# MainSheet.net
KiCad netlist of a schematic drawn in Altium Designer
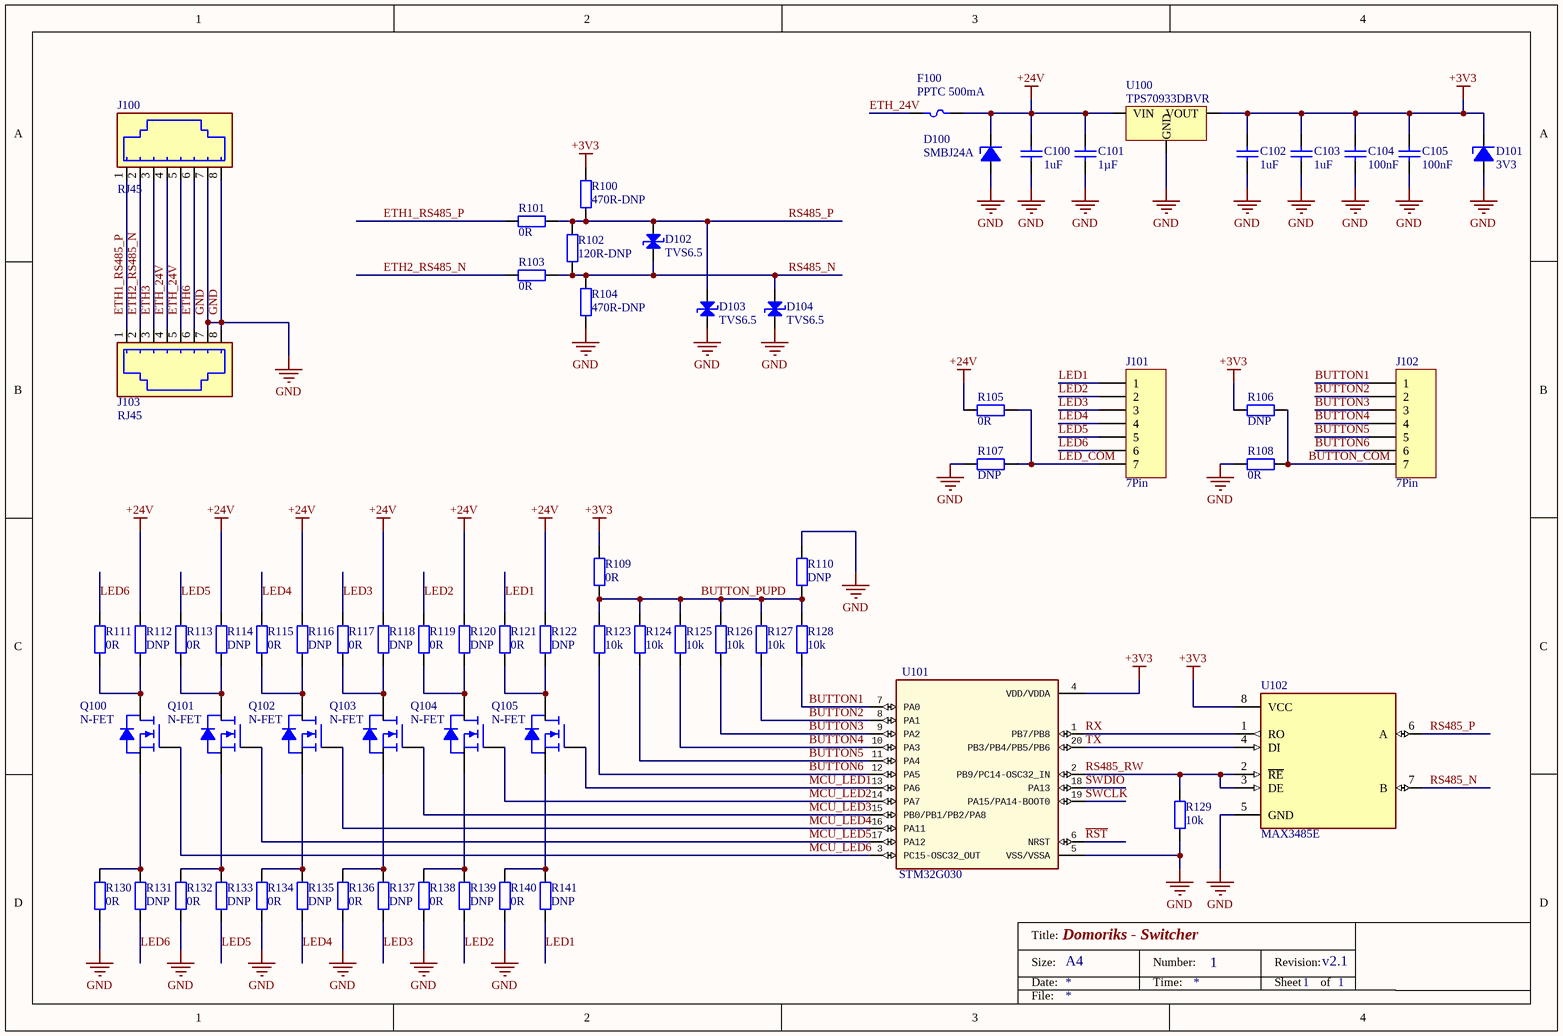
[diagram p0: MainSheet.SchDoc]

(export (version "E")
  (design (tool "Eeschema 10.0.6"))
  (components
    (comp (ref "C100") (value "1uF") (footprint "C0603") (libsource (lib "Library") (part "Capacitor")))
    (comp (ref "C101") (value "1µF") (footprint "C0603") (libsource (lib "Library") (part "Capacitor")))
    (comp (ref "C102") (value "1uF") (footprint "C0603") (libsource (lib "Library") (part "Capacitor")))
    (comp (ref "C103") (value "1uF") (footprint "C0603") (libsource (lib "Library") (part "Capacitor")))
    (comp (ref "C104") (value "100nF") (footprint "C0603") (libsource (lib "Library") (part "Capacitor")))
    (comp (ref "C105") (value "100nF") (footprint "C0603") (libsource (lib "Library") (part "Capacitor")))
    (comp (ref "D100") (value "SMBJ24A") (footprint "SMB") (libsource (lib "Library") (part "TVS Uni")))
    (comp (ref "D101") (value "3V3") (footprint "SOD323") (libsource (lib "MyLib") (part "TVS Uni")))
    (comp (ref "D102") (value "TVS6.5") (footprint "SOD323") (libsource (lib "Library") (part "TVS Bi")))
    (comp (ref "D103") (value "TVS6.5") (footprint "SOD323") (libsource (lib "Library") (part "TVS Bi")))
    (comp (ref "D104") (value "TVS6.5") (footprint "SOD323") (libsource (lib "Library") (part "TVS Bi")))
    (comp (ref "F100") (value "PPTC 500mA") (footprint "PPTC1812") (libsource (lib "Library") (part "Fuse")))
    (comp (ref "J100")
      (value "RJ45")
      (footprint "RJ45_RA")
      (description "Jack Modular Connector 8p8c (RJ45, Ethernet) Vertical Unshielded Cat5")
      (fields (field (name "MF") "Wurth Elektronik") (field (name "MP") "615008144221"))
      (libsource (lib "Library") (part "RJ45"))
    )
    (comp (ref "J101") (value "7Pin") (footprint "7Pin") (libsource (lib "Library") (part "7Pin")))
    (comp (ref "J102") (value "7Pin") (footprint "7Pin") (libsource (lib "Library") (part "7Pin")))
    (comp (ref "J103")
      (value "RJ45")
      (footprint "RJ45_RA")
      (description "Jack Modular Connector 8p8c (RJ45, Ethernet) Vertical Unshielded Cat5")
      (fields (field (name "MF") "Wurth Elektronik") (field (name "MP") "615008144221"))
      (libsource (lib "") (part "RJ45_1"))
    )
    (comp (ref "Q100") (value "N-FET") (footprint "SOT323") (libsource (lib "Library") (part "N-FET")))
    (comp (ref "Q101") (value "N-FET") (footprint "SOT323") (libsource (lib "Library") (part "N-FET")))
    (comp (ref "Q102") (value "N-FET") (footprint "SOT323") (libsource (lib "Library") (part "N-FET")))
    (comp (ref "Q103") (value "N-FET") (footprint "SOT323") (libsource (lib "Library") (part "N-FET")))
    (comp (ref "Q104") (value "N-FET") (footprint "SOT323") (libsource (lib "Library") (part "N-FET")))
    (comp (ref "Q105") (value "N-FET") (footprint "SOT323") (libsource (lib "Library") (part "N-FET")))
    (comp (ref "R100") (value "470R-DNP") (footprint "R0603") (libsource (lib "") (part "Resistor_2")))
    (comp (ref "R101") (value "0R") (footprint "R0603") (libsource (lib "Library") (part "Resistor")))
    (comp (ref "R102") (value "120R-DNP") (footprint "R0603") (libsource (lib "") (part "Resistor_2")))
    (comp (ref "R103") (value "0R") (footprint "R0603") (libsource (lib "Library") (part "Resistor")))
    (comp (ref "R104") (value "470R-DNP") (footprint "R0603") (libsource (lib "") (part "Resistor_2")))
    (comp (ref "R105") (value "0R") (footprint "R0603") (libsource (lib "") (part "Resistor_1")))
    (comp (ref "R106") (value "DNP") (footprint "R0603") (libsource (lib "") (part "Resistor_1")))
    (comp (ref "R107") (value "DNP") (footprint "R0603") (libsource (lib "") (part "Resistor_1")))
    (comp (ref "R108") (value "0R") (footprint "R0603") (libsource (lib "") (part "Resistor_1")))
    (comp (ref "R109") (value "0R") (footprint "R0603") (libsource (lib "Library") (part "Resistor")))
    (comp (ref "R110") (value "DNP") (footprint "R0603") (libsource (lib "Library") (part "Resistor")))
    (comp (ref "R111") (value "0R") (footprint "R0603") (libsource (lib "Library") (part "Resistor")))
    (comp (ref "R112") (value "DNP") (footprint "R0603") (libsource (lib "Library") (part "Resistor")))
    (comp (ref "R113") (value "0R") (footprint "R0603") (libsource (lib "Library") (part "Resistor")))
    (comp (ref "R114") (value "DNP") (footprint "R0603") (libsource (lib "Library") (part "Resistor")))
    (comp (ref "R115") (value "0R") (footprint "R0603") (libsource (lib "Library") (part "Resistor")))
    (comp (ref "R116") (value "DNP") (footprint "R0603") (libsource (lib "Library") (part "Resistor")))
    (comp (ref "R117") (value "0R") (footprint "R0603") (libsource (lib "Library") (part "Resistor")))
    (comp (ref "R118") (value "DNP") (footprint "R0603") (libsource (lib "Library") (part "Resistor")))
    (comp (ref "R119") (value "0R") (footprint "R0603") (libsource (lib "Library") (part "Resistor")))
    (comp (ref "R120") (value "DNP") (footprint "R0603") (libsource (lib "Library") (part "Resistor")))
    (comp (ref "R121") (value "0R") (footprint "R0603") (libsource (lib "Library") (part "Resistor")))
    (comp (ref "R122") (value "DNP") (footprint "R0603") (libsource (lib "Library") (part "Resistor")))
    (comp (ref "R123") (value "10k") (footprint "R0603") (libsource (lib "Library") (part "Resistor")))
    (comp (ref "R124") (value "10k") (footprint "R0603") (libsource (lib "Library") (part "Resistor")))
    (comp (ref "R125") (value "10k") (footprint "R0603") (libsource (lib "Library") (part "Resistor")))
    (comp (ref "R126") (value "10k") (footprint "R0603") (libsource (lib "Library") (part "Resistor")))
    (comp (ref "R127") (value "10k") (footprint "R0603") (libsource (lib "Library") (part "Resistor")))
    (comp (ref "R128") (value "10k") (footprint "R0603") (libsource (lib "Library") (part "Resistor")))
    (comp (ref "R129") (value "10k") (footprint "R0603") (libsource (lib "Library") (part "Resistor")))
    (comp (ref "R130") (value "0R") (footprint "R0603") (libsource (lib "Library") (part "Resistor")))
    (comp (ref "R131") (value "DNP") (footprint "R0603") (libsource (lib "Library") (part "Resistor")))
    (comp (ref "R132") (value "0R") (footprint "R0603") (libsource (lib "Library") (part "Resistor")))
    (comp (ref "R133") (value "DNP") (footprint "R0603") (libsource (lib "Library") (part "Resistor")))
    (comp (ref "R134") (value "0R") (footprint "R0603") (libsource (lib "Library") (part "Resistor")))
    (comp (ref "R135") (value "DNP") (footprint "R0603") (libsource (lib "Library") (part "Resistor")))
    (comp (ref "R136") (value "0R") (footprint "R0603") (libsource (lib "Library") (part "Resistor")))
    (comp (ref "R137") (value "DNP") (footprint "R0603") (libsource (lib "Library") (part "Resistor")))
    (comp (ref "R138") (value "0R") (footprint "R0603") (libsource (lib "Library") (part "Resistor")))
    (comp (ref "R139") (value "DNP") (footprint "R0603") (libsource (lib "Library") (part "Resistor")))
    (comp (ref "R140") (value "0R") (footprint "R0603") (libsource (lib "Library") (part "Resistor")))
    (comp (ref "R141") (value "DNP") (footprint "R0603") (libsource (lib "Library") (part "Resistor")))
    (comp (ref "U100")
      (value "TPS70933DBVR")
      (footprint "SOT-23-5")
      (fields (field (name "MP") "LP38690DT-5.0/NOPB") (field (name "MF") "Texas Instruments"))
      (libsource (lib "Schlib1") (part "LDO"))
    )
    (comp (ref "U101")
      (value "STM32G030")
      (footprint "TSSOP20")
      (fields
        (field (name "MANUFACTURER_PART_NUMBER") "STM32G030F6P6TR")
        (field (name "COPYRIGHT") "Copyright (C) 2022 Ultra Librarian. All rights reserved.")
      )
      (libsource (lib "Schlib1") (part "STM32G030"))
    )
    (comp (ref "U102")
      (value "MAX3485E")
      (footprint "SOIC-08")
      (description "1/1 Transceiver Half RS422, RS485 8-SOIC")
      (fields (field (name "MF") "Maxim Integrated") (field (name "MP") "MAX3485EESA+T"))
      (libsource (lib "Library") (part "MAX3485E"))
    )
  )
  (nets
    (net (code "1") (name "+3V3") (class "Default")
      (node (ref "C102") (pin "2") (pinfunction "2_2") (pintype "passive"))
      (node (ref "C103") (pin "2") (pinfunction "2_2") (pintype "passive"))
      (node (ref "C104") (pin "2") (pinfunction "2_2") (pintype "passive"))
      (node (ref "C105") (pin "2") (pinfunction "2_2") (pintype "passive"))
      (node (ref "D101") (pin "1") (pinfunction "1_1") (pintype "passive"))
      (node (ref "R100") (pin "2") (pinfunction "2_2") (pintype "passive"))
      (node (ref "R106") (pin "2") (pinfunction "2_2") (pintype "passive"))
      (node (ref "R109") (pin "2") (pinfunction "2_2") (pintype "passive"))
      (node (ref "U100") (pin "5") (pinfunction "VOUT_5") (pintype "power_in"))
      (node (ref "U101") (pin "4") (pinfunction "VDD/VDDA_4") (pintype "power_in"))
      (node (ref "U102") (pin "8") (pinfunction "VCC_8") (pintype "power_in"))
    )
    (net (code "2") (name "+24V") (class "Default")
      (node (ref "C100") (pin "2") (pinfunction "2_2") (pintype "passive"))
      (node (ref "C101") (pin "2") (pinfunction "2_2") (pintype "passive"))
      (node (ref "D100") (pin "1") (pinfunction "1_1") (pintype "passive"))
      (node (ref "F100") (pin "2") (pinfunction "2_2") (pintype "passive"))
      (node (ref "R105") (pin "2") (pinfunction "2_2") (pintype "passive"))
      (node (ref "R112") (pin "2") (pinfunction "2_2") (pintype "passive"))
      (node (ref "R114") (pin "2") (pinfunction "2_2") (pintype "passive"))
      (node (ref "R116") (pin "2") (pinfunction "2_2") (pintype "passive"))
      (node (ref "R118") (pin "2") (pinfunction "2_2") (pintype "passive"))
      (node (ref "R120") (pin "2") (pinfunction "2_2") (pintype "passive"))
      (node (ref "R122") (pin "2") (pinfunction "2_2") (pintype "passive"))
      (node (ref "U100") (pin "1") (pinfunction "VIN_1") (pintype "power_in"))
    )
    (net (code "3") (name "/BUTTON1") (class "Default")
      (node (ref "J102") (pin "1") (pinfunction "1_1") (pintype "passive"))
      (node (ref "R128") (pin "1") (pinfunction "1_1") (pintype "passive"))
      (node (ref "U101") (pin "7") (pinfunction "PA0_7") (pintype "bidirectional"))
    )
    (net (code "4") (name "/BUTTON2") (class "Default")
      (node (ref "J102") (pin "2") (pinfunction "2_2") (pintype "passive"))
      (node (ref "R127") (pin "1") (pinfunction "1_1") (pintype "passive"))
      (node (ref "U101") (pin "8") (pinfunction "PA1_8") (pintype "bidirectional"))
    )
    (net (code "5") (name "/BUTTON3") (class "Default")
      (node (ref "J102") (pin "3") (pinfunction "3_3") (pintype "passive"))
      (node (ref "R126") (pin "1") (pinfunction "1_1") (pintype "passive"))
      (node (ref "U101") (pin "9") (pinfunction "PA2_9") (pintype "bidirectional"))
    )
    (net (code "6") (name "/BUTTON4") (class "Default")
      (node (ref "J102") (pin "4") (pinfunction "4_4") (pintype "passive"))
      (node (ref "R125") (pin "1") (pinfunction "1_1") (pintype "passive"))
      (node (ref "U101") (pin "10") (pinfunction "PA3_10") (pintype "bidirectional"))
    )
    (net (code "7") (name "/BUTTON5") (class "Default")
      (node (ref "J102") (pin "5") (pinfunction "5_5") (pintype "passive"))
      (node (ref "R124") (pin "1") (pinfunction "1_1") (pintype "passive"))
      (node (ref "U101") (pin "11") (pinfunction "PA4_11") (pintype "bidirectional"))
    )
    (net (code "8") (name "/BUTTON6") (class "Default")
      (node (ref "J102") (pin "6") (pinfunction "6_6") (pintype "passive"))
      (node (ref "R123") (pin "1") (pinfunction "1_1") (pintype "passive"))
      (node (ref "U101") (pin "12") (pinfunction "PA5_12") (pintype "bidirectional"))
    )
    (net (code "9") (name "/BUTTON_COM") (class "Default")
      (node (ref "J102") (pin "7") (pinfunction "7_7") (pintype "passive"))
      (node (ref "R106") (pin "1") (pinfunction "1_1") (pintype "passive"))
      (node (ref "R108") (pin "1") (pinfunction "1_1") (pintype "passive"))
    )
    (net (code "10") (name "/BUTTON_PUPD") (class "Default")
      (node (ref "R109") (pin "1") (pinfunction "1_1") (pintype "passive"))
      (node (ref "R110") (pin "1") (pinfunction "1_1") (pintype "passive"))
      (node (ref "R123") (pin "2") (pinfunction "2_2") (pintype "passive"))
      (node (ref "R124") (pin "2") (pinfunction "2_2") (pintype "passive"))
      (node (ref "R125") (pin "2") (pinfunction "2_2") (pintype "passive"))
      (node (ref "R126") (pin "2") (pinfunction "2_2") (pintype "passive"))
      (node (ref "R127") (pin "2") (pinfunction "2_2") (pintype "passive"))
      (node (ref "R128") (pin "2") (pinfunction "2_2") (pintype "passive"))
    )
    (net (code "11") (name "/ETH1_RS485_P") (class "Default")
      (node (ref "J100") (pin "1") (pinfunction "8_1") (pintype "passive"))
      (node (ref "J103") (pin "1") (pinfunction "8_1") (pintype "passive"))
      (node (ref "R101") (pin "1") (pinfunction "1_1") (pintype "passive"))
    )
    (net (code "12") (name "/ETH2_RS485_N") (class "Default")
      (node (ref "J100") (pin "2") (pinfunction "7_2") (pintype "passive"))
      (node (ref "J103") (pin "2") (pinfunction "7_2") (pintype "passive"))
      (node (ref "R103") (pin "1") (pinfunction "1_1") (pintype "passive"))
    )
    (net (code "13") (name "/ETH3") (class "Default")
      (node (ref "J100") (pin "3") (pinfunction "6_3") (pintype "passive"))
      (node (ref "J103") (pin "3") (pinfunction "6_3") (pintype "passive"))
    )
    (net (code "14") (name "/ETH6") (class "Default")
      (node (ref "J100") (pin "6") (pinfunction "3_6") (pintype "passive"))
      (node (ref "J103") (pin "6") (pinfunction "3_6") (pintype "passive"))
    )
    (net (code "15") (name "/ETH_24V") (class "Default")
      (node (ref "F100") (pin "1") (pinfunction "1_1") (pintype "passive"))
      (node (ref "J100") (pin "4") (pinfunction "5_4") (pintype "passive"))
      (node (ref "J100") (pin "5") (pinfunction "4_5") (pintype "passive"))
      (node (ref "J103") (pin "4") (pinfunction "5_4") (pintype "passive"))
      (node (ref "J103") (pin "5") (pinfunction "4_5") (pintype "passive"))
    )
    (net (code "16") (name "/LED1") (class "Default")
      (node (ref "J101") (pin "1") (pinfunction "1_1") (pintype "passive"))
      (node (ref "R121") (pin "2") (pinfunction "2_2") (pintype "passive"))
      (node (ref "R141") (pin "1") (pinfunction "1_1") (pintype "passive"))
    )
    (net (code "17") (name "/LED2") (class "Default")
      (node (ref "J101") (pin "2") (pinfunction "2_2") (pintype "passive"))
      (node (ref "R119") (pin "2") (pinfunction "2_2") (pintype "passive"))
      (node (ref "R139") (pin "1") (pinfunction "1_1") (pintype "passive"))
    )
    (net (code "18") (name "/LED3") (class "Default")
      (node (ref "J101") (pin "3") (pinfunction "3_3") (pintype "passive"))
      (node (ref "R117") (pin "2") (pinfunction "2_2") (pintype "passive"))
      (node (ref "R137") (pin "1") (pinfunction "1_1") (pintype "passive"))
    )
    (net (code "19") (name "/LED4") (class "Default")
      (node (ref "J101") (pin "4") (pinfunction "4_4") (pintype "passive"))
      (node (ref "R115") (pin "2") (pinfunction "2_2") (pintype "passive"))
      (node (ref "R135") (pin "1") (pinfunction "1_1") (pintype "passive"))
    )
    (net (code "20") (name "/LED5") (class "Default")
      (node (ref "J101") (pin "5") (pinfunction "5_5") (pintype "passive"))
      (node (ref "R113") (pin "2") (pinfunction "2_2") (pintype "passive"))
      (node (ref "R133") (pin "1") (pinfunction "1_1") (pintype "passive"))
    )
    (net (code "21") (name "/LED6") (class "Default")
      (node (ref "J101") (pin "6") (pinfunction "6_6") (pintype "passive"))
      (node (ref "R111") (pin "2") (pinfunction "2_2") (pintype "passive"))
      (node (ref "R131") (pin "1") (pinfunction "1_1") (pintype "passive"))
    )
    (net (code "22") (name "/LED_COM") (class "Default")
      (node (ref "J101") (pin "7") (pinfunction "7_7") (pintype "passive"))
      (node (ref "R105") (pin "1") (pinfunction "1_1") (pintype "passive"))
      (node (ref "R107") (pin "1") (pinfunction "1_1") (pintype "passive"))
    )
    (net (code "23") (name "/MCU_LED1") (class "Default")
      (node (ref "Q105") (pin "1") (pinfunction "G_1") (pintype "passive"))
      (node (ref "U101") (pin "13") (pinfunction "PA6_13") (pintype "bidirectional"))
    )
    (net (code "24") (name "/MCU_LED2") (class "Default")
      (node (ref "Q104") (pin "1") (pinfunction "G_1") (pintype "passive"))
      (node (ref "U101") (pin "14") (pinfunction "PA7_14") (pintype "bidirectional"))
    )
    (net (code "25") (name "/MCU_LED3") (class "Default")
      (node (ref "Q103") (pin "1") (pinfunction "G_1") (pintype "passive"))
      (node (ref "U101") (pin "15") (pinfunction "PB0/PB1/PB2/PA8_15") (pintype "bidirectional"))
    )
    (net (code "26") (name "/MCU_LED4") (class "Default")
      (node (ref "Q102") (pin "1") (pinfunction "G_1") (pintype "passive"))
      (node (ref "U101") (pin "16") (pinfunction "PA11_16") (pintype "bidirectional"))
    )
    (net (code "27") (name "/MCU_LED5") (class "Default")
      (node (ref "Q101") (pin "1") (pinfunction "G_1") (pintype "passive"))
      (node (ref "U101") (pin "17") (pinfunction "PA12_17") (pintype "bidirectional"))
    )
    (net (code "28") (name "/MCU_LED6") (class "Default")
      (node (ref "Q100") (pin "1") (pinfunction "G_1") (pintype "passive"))
      (node (ref "U101") (pin "3") (pinfunction "PC15-OSC32_OUT_3") (pintype "bidirectional"))
    )
    (net (code "29") (name "/RS485_N") (class "Default")
      (node (ref "D102") (pin "1") (pinfunction "1_1") (pintype "passive"))
      (node (ref "D104") (pin "2") (pinfunction "2_2") (pintype "passive"))
      (node (ref "R102") (pin "1") (pinfunction "1_1") (pintype "passive"))
      (node (ref "R103") (pin "2") (pinfunction "2_2") (pintype "passive"))
      (node (ref "R104") (pin "2") (pinfunction "2_2") (pintype "passive"))
      (node (ref "U102") (pin "7") (pinfunction "B_7") (pintype "bidirectional"))
    )
    (net (code "30") (name "/RS485_P") (class "Default")
      (node (ref "D102") (pin "2") (pinfunction "2_2") (pintype "passive"))
      (node (ref "D103") (pin "2") (pinfunction "2_2") (pintype "passive"))
      (node (ref "R100") (pin "1") (pinfunction "1_1") (pintype "passive"))
      (node (ref "R101") (pin "2") (pinfunction "2_2") (pintype "passive"))
      (node (ref "R102") (pin "2") (pinfunction "2_2") (pintype "passive"))
      (node (ref "U102") (pin "6") (pinfunction "A_6") (pintype "bidirectional"))
    )
    (net (code "31") (name "/RS485_RW") (class "Default")
      (node (ref "R129") (pin "2") (pinfunction "2_2") (pintype "passive"))
      (node (ref "U101") (pin "2") (pinfunction "PB9/PC14-OSC32_IN_2") (pintype "bidirectional"))
      (node (ref "U102") (pin "2") (pinfunction "~{RE}_2") (pintype "input"))
      (node (ref "U102") (pin "3") (pinfunction "DE_3") (pintype "input"))
    )
    (net (code "32") (name "/RX") (class "Default")
      (node (ref "U101") (pin "1") (pinfunction "PB7/PB8_1") (pintype "bidirectional"))
      (node (ref "U102") (pin "1") (pinfunction "RO_1") (pintype "output"))
    )
    (net (code "33") (name "/SWCLK") (class "Default")
      (node (ref "U101") (pin "19") (pinfunction "PA15/PA14-BOOT0_19") (pintype "bidirectional"))
    )
    (net (code "34") (name "/SWDIO") (class "Default")
      (node (ref "U101") (pin "18") (pinfunction "PA13_18") (pintype "bidirectional"))
    )
    (net (code "35") (name "/TX") (class "Default")
      (node (ref "U101") (pin "20") (pinfunction "PB3/PB4/PB5/PB6_20") (pintype "bidirectional"))
      (node (ref "U102") (pin "4") (pinfunction "DI_4") (pintype "input"))
    )
    (net (code "36") (name "/~{RST}") (class "Default")
      (node (ref "U101") (pin "6") (pinfunction "NRST_6") (pintype "bidirectional"))
    )
    (net (code "37") (name "GND") (class "Default")
      (node (ref "C100") (pin "1") (pinfunction "1_1") (pintype "passive"))
      (node (ref "C101") (pin "1") (pinfunction "1_1") (pintype "passive"))
      (node (ref "C102") (pin "1") (pinfunction "1_1") (pintype "passive"))
      (node (ref "C103") (pin "1") (pinfunction "1_1") (pintype "passive"))
      (node (ref "C104") (pin "1") (pinfunction "1_1") (pintype "passive"))
      (node (ref "C105") (pin "1") (pinfunction "1_1") (pintype "passive"))
      (node (ref "D100") (pin "2") (pinfunction "2_2") (pintype "passive"))
      (node (ref "D101") (pin "2") (pinfunction "2_2") (pintype "passive"))
      (node (ref "D103") (pin "1") (pinfunction "1_1") (pintype "passive"))
      (node (ref "D104") (pin "1") (pinfunction "1_1") (pintype "passive"))
      (node (ref "J100") (pin "7") (pinfunction "2_7") (pintype "passive"))
      (node (ref "J100") (pin "8") (pinfunction "1_8") (pintype "passive"))
      (node (ref "J103") (pin "7") (pinfunction "2_7") (pintype "passive"))
      (node (ref "J103") (pin "8") (pinfunction "1_8") (pintype "passive"))
      (node (ref "R104") (pin "1") (pinfunction "1_1") (pintype "passive"))
      (node (ref "R107") (pin "2") (pinfunction "2_2") (pintype "passive"))
      (node (ref "R108") (pin "2") (pinfunction "2_2") (pintype "passive"))
      (node (ref "R110") (pin "2") (pinfunction "2_2") (pintype "passive"))
      (node (ref "R129") (pin "1") (pinfunction "1_1") (pintype "passive"))
      (node (ref "R130") (pin "1") (pinfunction "1_1") (pintype "passive"))
      (node (ref "R132") (pin "1") (pinfunction "1_1") (pintype "passive"))
      (node (ref "R134") (pin "1") (pinfunction "1_1") (pintype "passive"))
      (node (ref "R136") (pin "1") (pinfunction "1_1") (pintype "passive"))
      (node (ref "R138") (pin "1") (pinfunction "1_1") (pintype "passive"))
      (node (ref "R140") (pin "1") (pinfunction "1_1") (pintype "passive"))
      (node (ref "U100") (pin "2") (pinfunction "GND_2") (pintype "passive"))
      (node (ref "U101") (pin "5") (pinfunction "VSS/VSSA_5") (pintype "power_in"))
      (node (ref "U102") (pin "5") (pinfunction "GND_5") (pintype "power_in"))
    )
    (net (code "38") (name "Net-(Q100-D)") (class "Default")
      (node (ref "Q100") (pin "3") (pinfunction "D_3") (pintype "passive"))
      (node (ref "R111") (pin "1") (pinfunction "1_1") (pintype "passive"))
      (node (ref "R112") (pin "1") (pinfunction "1_1") (pintype "passive"))
    )
    (net (code "39") (name "Net-(Q100-S)") (class "Default")
      (node (ref "Q100") (pin "2") (pinfunction "S_2") (pintype "passive"))
      (node (ref "R130") (pin "2") (pinfunction "2_2") (pintype "passive"))
      (node (ref "R131") (pin "2") (pinfunction "2_2") (pintype "passive"))
    )
    (net (code "40") (name "Net-(Q101-D)") (class "Default")
      (node (ref "Q101") (pin "3") (pinfunction "D_3") (pintype "passive"))
      (node (ref "R113") (pin "1") (pinfunction "1_1") (pintype "passive"))
      (node (ref "R114") (pin "1") (pinfunction "1_1") (pintype "passive"))
    )
    (net (code "41") (name "Net-(Q101-S)") (class "Default")
      (node (ref "Q101") (pin "2") (pinfunction "S_2") (pintype "passive"))
      (node (ref "R132") (pin "2") (pinfunction "2_2") (pintype "passive"))
      (node (ref "R133") (pin "2") (pinfunction "2_2") (pintype "passive"))
    )
    (net (code "42") (name "Net-(Q102-D)") (class "Default")
      (node (ref "Q102") (pin "3") (pinfunction "D_3") (pintype "passive"))
      (node (ref "R115") (pin "1") (pinfunction "1_1") (pintype "passive"))
      (node (ref "R116") (pin "1") (pinfunction "1_1") (pintype "passive"))
    )
    (net (code "43") (name "Net-(Q102-S)") (class "Default")
      (node (ref "Q102") (pin "2") (pinfunction "S_2") (pintype "passive"))
      (node (ref "R134") (pin "2") (pinfunction "2_2") (pintype "passive"))
      (node (ref "R135") (pin "2") (pinfunction "2_2") (pintype "passive"))
    )
    (net (code "44") (name "Net-(Q103-D)") (class "Default")
      (node (ref "Q103") (pin "3") (pinfunction "D_3") (pintype "passive"))
      (node (ref "R117") (pin "1") (pinfunction "1_1") (pintype "passive"))
      (node (ref "R118") (pin "1") (pinfunction "1_1") (pintype "passive"))
    )
    (net (code "45") (name "Net-(Q103-S)") (class "Default")
      (node (ref "Q103") (pin "2") (pinfunction "S_2") (pintype "passive"))
      (node (ref "R136") (pin "2") (pinfunction "2_2") (pintype "passive"))
      (node (ref "R137") (pin "2") (pinfunction "2_2") (pintype "passive"))
    )
    (net (code "46") (name "Net-(Q104-D)") (class "Default")
      (node (ref "Q104") (pin "3") (pinfunction "D_3") (pintype "passive"))
      (node (ref "R119") (pin "1") (pinfunction "1_1") (pintype "passive"))
      (node (ref "R120") (pin "1") (pinfunction "1_1") (pintype "passive"))
    )
    (net (code "47") (name "Net-(Q104-S)") (class "Default")
      (node (ref "Q104") (pin "2") (pinfunction "S_2") (pintype "passive"))
      (node (ref "R138") (pin "2") (pinfunction "2_2") (pintype "passive"))
      (node (ref "R139") (pin "2") (pinfunction "2_2") (pintype "passive"))
    )
    (net (code "48") (name "Net-(Q105-D)") (class "Default")
      (node (ref "Q105") (pin "3") (pinfunction "D_3") (pintype "passive"))
      (node (ref "R121") (pin "1") (pinfunction "1_1") (pintype "passive"))
      (node (ref "R122") (pin "1") (pinfunction "1_1") (pintype "passive"))
    )
    (net (code "49") (name "Net-(Q105-S)") (class "Default")
      (node (ref "Q105") (pin "2") (pinfunction "S_2") (pintype "passive"))
      (node (ref "R140") (pin "2") (pinfunction "2_2") (pintype "passive"))
      (node (ref "R141") (pin "2") (pinfunction "2_2") (pintype "passive"))
    )
  )
)
